# 05_BANK_5_6.net
KiCad netlist of a schematic drawn in Altium Designer
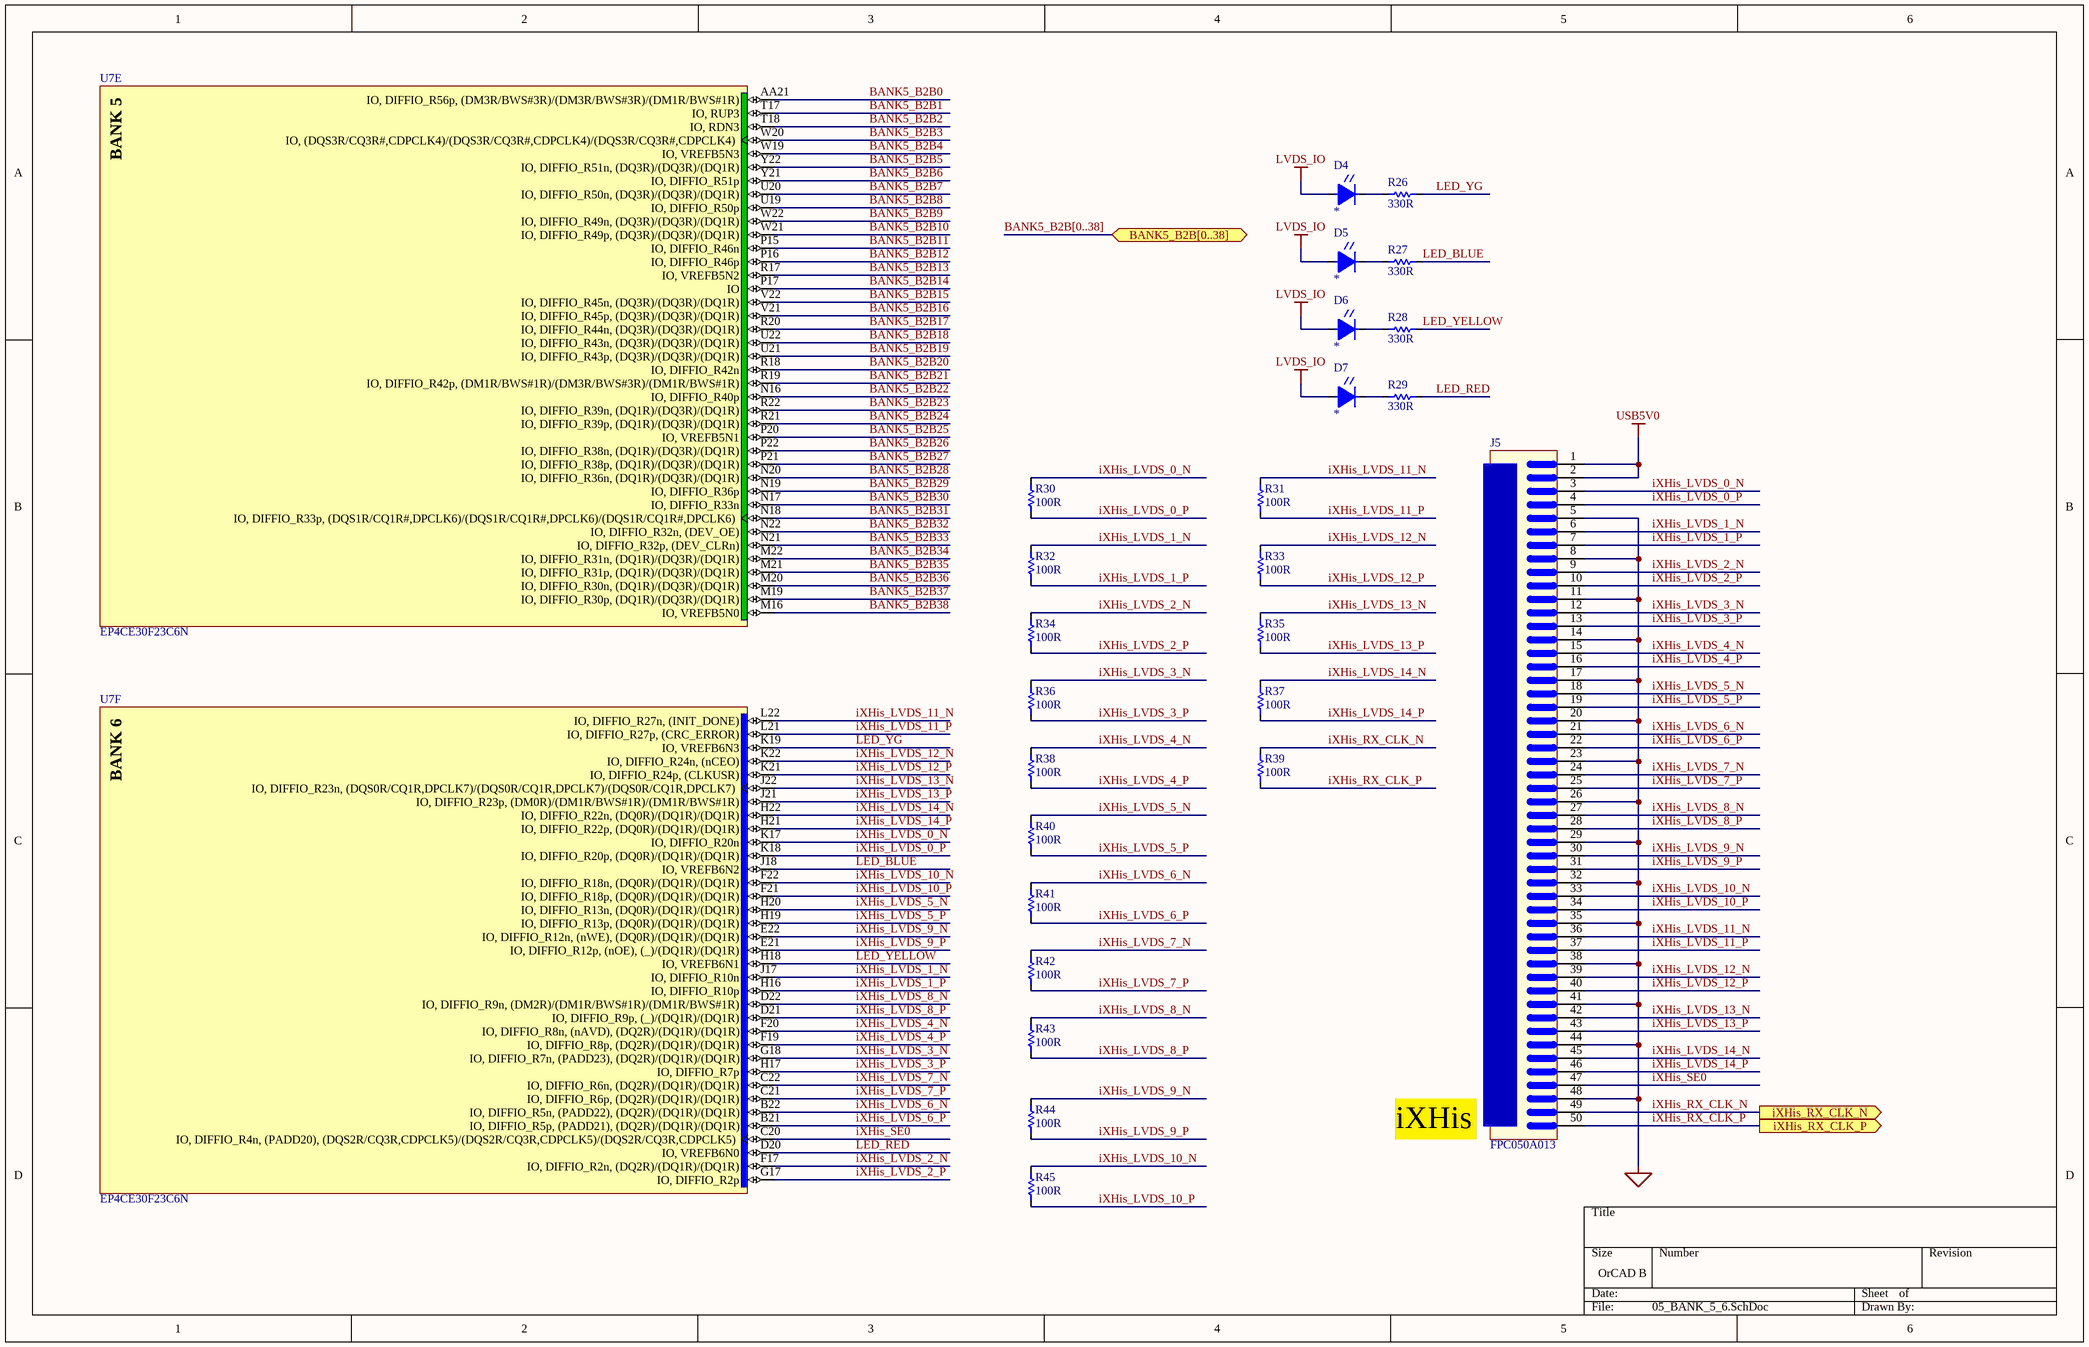
[diagram p0: 05_BANK_5_6.SchDoc]

(export (version "E")
  (design (tool "Eeschema 10.0.6"))
  (components
    (comp (ref "D4")
      (value "*")
      (footprint "LED0603")
      (description "LED,Yellow Green,2V,20mA,0603")
      (libsource (lib "AD15_schlib") (part "LED YellowGreen0603"))
    )
    (comp (ref "D5")
      (value "*")
      (footprint "LED0603")
      (description "LED,Blue,3.4V,20mA,0603")
      (libsource (lib "AD15_schlib") (part "LED Blue0603"))
    )
    (comp (ref "D6")
      (value "*")
      (footprint "LED0603")
      (description "LED,Yellow,2V,20mA,0603")
      (libsource (lib "AD15_schlib") (part "LED Yellow0603"))
    )
    (comp (ref "D7")
      (value "*")
      (footprint "LED0603")
      (description "LED,Super Red,2V,20mA,0603")
      (libsource (lib "AD15_schlib") (part "LED SuperRed0603"))
    )
    (comp (ref "J5")
      (value "FPC050A013")
      (footprint "FPC050A013")
      (description "FFC socket,50-Pin,Vertical,0.5mm Pitch,SMD")
      (libsource (lib "AD15_schlib") (part "FPC0.5mm_05"))
    )
    (comp (ref "R26")
      (value "330R")
      (footprint "R0402")
      (description "RES,330R,1%,1/16W,0402")
      (libsource (lib "R0402") (part "RES0111"))
    )
    (comp (ref "R27")
      (value "330R")
      (footprint "R0402")
      (description "RES,330R,1%,1/16W,0402")
      (libsource (lib "R0402") (part "RES0111"))
    )
    (comp (ref "R28")
      (value "330R")
      (footprint "R0402")
      (description "RES,330R,1%,1/16W,0402")
      (libsource (lib "R0402") (part "RES0111"))
    )
    (comp (ref "R29")
      (value "330R")
      (footprint "R0402")
      (description "RES,330R,1%,1/16W,0402")
      (libsource (lib "R0402") (part "RES0111"))
    )
    (comp (ref "R30")
      (value "100R")
      (footprint "R0402")
      (description "RES,100R,1%,1/16W,0402")
      (libsource (lib "R0402") (part "RES019"))
    )
    (comp (ref "R31")
      (value "100R")
      (footprint "R0402")
      (description "RES,100R,1%,1/16W,0402")
      (libsource (lib "R0402") (part "RES019"))
    )
    (comp (ref "R32")
      (value "100R")
      (footprint "R0402")
      (description "RES,100R,1%,1/16W,0402")
      (libsource (lib "R0402") (part "RES019"))
    )
    (comp (ref "R33")
      (value "100R")
      (footprint "R0402")
      (description "RES,100R,1%,1/16W,0402")
      (libsource (lib "R0402") (part "RES019"))
    )
    (comp (ref "R34")
      (value "100R")
      (footprint "R0402")
      (description "RES,100R,1%,1/16W,0402")
      (libsource (lib "R0402") (part "RES019"))
    )
    (comp (ref "R35")
      (value "100R")
      (footprint "R0402")
      (description "RES,100R,1%,1/16W,0402")
      (libsource (lib "R0402") (part "RES019"))
    )
    (comp (ref "R36")
      (value "100R")
      (footprint "R0402")
      (description "RES,100R,1%,1/16W,0402")
      (libsource (lib "R0402") (part "RES019"))
    )
    (comp (ref "R37")
      (value "100R")
      (footprint "R0402")
      (description "RES,100R,1%,1/16W,0402")
      (libsource (lib "R0402") (part "RES019"))
    )
    (comp (ref "R38")
      (value "100R")
      (footprint "R0402")
      (description "RES,100R,1%,1/16W,0402")
      (libsource (lib "R0402") (part "RES019"))
    )
    (comp (ref "R39")
      (value "100R")
      (footprint "R0402")
      (description "RES,100R,1%,1/16W,0402")
      (libsource (lib "R0402") (part "RES019"))
    )
    (comp (ref "R40")
      (value "100R")
      (footprint "R0402")
      (description "RES,100R,1%,1/16W,0402")
      (libsource (lib "R0402") (part "RES019"))
    )
    (comp (ref "R41")
      (value "100R")
      (footprint "R0402")
      (description "RES,100R,1%,1/16W,0402")
      (libsource (lib "R0402") (part "RES019"))
    )
    (comp (ref "R42")
      (value "100R")
      (footprint "R0402")
      (description "RES,100R,1%,1/16W,0402")
      (libsource (lib "R0402") (part "RES019"))
    )
    (comp (ref "R43")
      (value "100R")
      (footprint "R0402")
      (description "RES,100R,1%,1/16W,0402")
      (libsource (lib "R0402") (part "RES019"))
    )
    (comp (ref "R44")
      (value "100R")
      (footprint "R0402")
      (description "RES,100R,1%,1/16W,0402")
      (libsource (lib "R0402") (part "RES019"))
    )
    (comp (ref "R45")
      (value "100R")
      (footprint "R0402")
      (description "RES,100R,1%,1/16W,0402")
      (libsource (lib "R0402") (part "RES019"))
    )
    (comp (ref "U7")
      (value "EP4CE30F23C6N")
      (footprint "FBGA484_EP4CE30F23C6N")
      (description "IC,FPGA,28848 LEs,Speed-6,FBGA484")
      (libsource (lib "AD15_Altera_schlib") (part "EP4CE30F23C6N"))
    )
  )
  (nets
    (net (code "1") (name "/BANK5_B2B0") (class "Default")
      (node (ref "U7") (pin "AA21") (pinfunction "IO,_DIFFIO_R56p,_(DM3R/BWS#3R)/(DM3R/BWS#3R)/(DM1R/BWS#1R)_AA21") (pintype "bidirectional"))
    )
    (net (code "2") (name "/BANK5_B2B1") (class "Default")
      (node (ref "U7") (pin "T17") (pinfunction "IO,_RUP3_T17") (pintype "bidirectional"))
    )
    (net (code "3") (name "/BANK5_B2B2") (class "Default")
      (node (ref "U7") (pin "T18") (pinfunction "IO,_RDN3_T18") (pintype "bidirectional"))
    )
    (net (code "4") (name "/BANK5_B2B3") (class "Default")
      (node (ref "U7") (pin "W20") (pinfunction "IO,_(DQS3R/CQ3R#,CDPCLK4)/(DQS3R/CQ3R#,CDPCLK4)/(DQS3R/CQ3R#,CDPCLK4)_W20") (pintype "bidirectional"))
    )
    (net (code "5") (name "/BANK5_B2B4") (class "Default")
      (node (ref "U7") (pin "W19") (pinfunction "IO,_VREFB5N3_W19") (pintype "bidirectional"))
    )
    (net (code "6") (name "/BANK5_B2B5") (class "Default")
      (node (ref "U7") (pin "Y22") (pinfunction "IO,_DIFFIO_R51n,_(DQ3R)/(DQ3R)/(DQ1R)_Y22") (pintype "bidirectional"))
    )
    (net (code "7") (name "/BANK5_B2B6") (class "Default")
      (node (ref "U7") (pin "Y21") (pinfunction "IO,_DIFFIO_R51p_Y21") (pintype "bidirectional"))
    )
    (net (code "8") (name "/BANK5_B2B7") (class "Default")
      (node (ref "U7") (pin "U20") (pinfunction "IO,_DIFFIO_R50n,_(DQ3R)/(DQ3R)/(DQ1R)_U20") (pintype "bidirectional"))
    )
    (net (code "9") (name "/BANK5_B2B8") (class "Default")
      (node (ref "U7") (pin "U19") (pinfunction "IO,_DIFFIO_R50p_U19") (pintype "bidirectional"))
    )
    (net (code "10") (name "/BANK5_B2B9") (class "Default")
      (node (ref "U7") (pin "W22") (pinfunction "IO,_DIFFIO_R49n,_(DQ3R)/(DQ3R)/(DQ1R)_W22") (pintype "bidirectional"))
    )
    (net (code "11") (name "/BANK5_B2B10") (class "Default")
      (node (ref "U7") (pin "W21") (pinfunction "IO,_DIFFIO_R49p,_(DQ3R)/(DQ3R)/(DQ1R)_W21") (pintype "bidirectional"))
    )
    (net (code "12") (name "/BANK5_B2B11") (class "Default")
      (node (ref "U7") (pin "P15") (pinfunction "IO,_DIFFIO_R46n_P15") (pintype "bidirectional"))
    )
    (net (code "13") (name "/BANK5_B2B12") (class "Default")
      (node (ref "U7") (pin "P16") (pinfunction "IO,_DIFFIO_R46p_P16") (pintype "bidirectional"))
    )
    (net (code "14") (name "/BANK5_B2B13") (class "Default")
      (node (ref "U7") (pin "R17") (pinfunction "IO,_VREFB5N2_R17") (pintype "bidirectional"))
    )
    (net (code "15") (name "/BANK5_B2B14") (class "Default")
      (node (ref "U7") (pin "P17") (pinfunction "IO_P17") (pintype "bidirectional"))
    )
    (net (code "16") (name "/BANK5_B2B15") (class "Default")
      (node (ref "U7") (pin "V22") (pinfunction "IO,_DIFFIO_R45n,_(DQ3R)/(DQ3R)/(DQ1R)_V22") (pintype "bidirectional"))
    )
    (net (code "17") (name "/BANK5_B2B16") (class "Default")
      (node (ref "U7") (pin "V21") (pinfunction "IO,_DIFFIO_R45p,_(DQ3R)/(DQ3R)/(DQ1R)_V21") (pintype "bidirectional"))
    )
    (net (code "18") (name "/BANK5_B2B17") (class "Default")
      (node (ref "U7") (pin "R20") (pinfunction "IO,_DIFFIO_R44n,_(DQ3R)/(DQ3R)/(DQ1R)_R20") (pintype "bidirectional"))
    )
    (net (code "19") (name "/BANK5_B2B18") (class "Default")
      (node (ref "U7") (pin "U22") (pinfunction "IO,_DIFFIO_R43n,_(DQ3R)/(DQ3R)/(DQ1R)_U22") (pintype "bidirectional"))
    )
    (net (code "20") (name "/BANK5_B2B19") (class "Default")
      (node (ref "U7") (pin "U21") (pinfunction "IO,_DIFFIO_R43p,_(DQ3R)/(DQ3R)/(DQ1R)_U21") (pintype "bidirectional"))
    )
    (net (code "21") (name "/BANK5_B2B20") (class "Default")
      (node (ref "U7") (pin "R18") (pinfunction "IO,_DIFFIO_R42n_R18") (pintype "bidirectional"))
    )
    (net (code "22") (name "/BANK5_B2B21") (class "Default")
      (node (ref "U7") (pin "R19") (pinfunction "IO,_DIFFIO_R42p,_(DM1R/BWS#1R)/(DM3R/BWS#3R)/(DM1R/BWS#1R)_R19") (pintype "bidirectional"))
    )
    (net (code "23") (name "/BANK5_B2B22") (class "Default")
      (node (ref "U7") (pin "N16") (pinfunction "IO,_DIFFIO_R40p_N16") (pintype "bidirectional"))
    )
    (net (code "24") (name "/BANK5_B2B23") (class "Default")
      (node (ref "U7") (pin "R22") (pinfunction "IO,_DIFFIO_R39n,_(DQ1R)/(DQ3R)/(DQ1R)_R22") (pintype "bidirectional"))
    )
    (net (code "25") (name "/BANK5_B2B24") (class "Default")
      (node (ref "U7") (pin "R21") (pinfunction "IO,_DIFFIO_R39p,_(DQ1R)/(DQ3R)/(DQ1R)_R21") (pintype "bidirectional"))
    )
    (net (code "26") (name "/BANK5_B2B25") (class "Default")
      (node (ref "U7") (pin "P20") (pinfunction "IO,_VREFB5N1_P20") (pintype "bidirectional"))
    )
    (net (code "27") (name "/BANK5_B2B26") (class "Default")
      (node (ref "U7") (pin "P22") (pinfunction "IO,_DIFFIO_R38n,_(DQ1R)/(DQ3R)/(DQ1R)_P22") (pintype "bidirectional"))
    )
    (net (code "28") (name "/BANK5_B2B27") (class "Default")
      (node (ref "U7") (pin "P21") (pinfunction "IO,_DIFFIO_R38p,_(DQ1R)/(DQ3R)/(DQ1R)_P21") (pintype "bidirectional"))
    )
    (net (code "29") (name "/BANK5_B2B28") (class "Default")
      (node (ref "U7") (pin "N20") (pinfunction "IO,_DIFFIO_R36n,_(DQ1R)/(DQ3R)/(DQ1R)_N20") (pintype "bidirectional"))
    )
    (net (code "30") (name "/BANK5_B2B29") (class "Default")
      (node (ref "U7") (pin "N19") (pinfunction "IO,_DIFFIO_R36p_N19") (pintype "bidirectional"))
    )
    (net (code "31") (name "/BANK5_B2B30") (class "Default")
      (node (ref "U7") (pin "N17") (pinfunction "IO,_DIFFIO_R33n_N17") (pintype "bidirectional"))
    )
    (net (code "32") (name "/BANK5_B2B31") (class "Default")
      (node (ref "U7") (pin "N18") (pinfunction "IO,_DIFFIO_R33p,_(DQS1R/CQ1R#,DPCLK6)/(DQS1R/CQ1R#,DPCLK6)/(DQS1R/CQ1R#,DPCLK6)_N18") (pintype "bidirectional"))
    )
    (net (code "33") (name "/BANK5_B2B32") (class "Default")
      (node (ref "U7") (pin "N22") (pinfunction "IO,_DIFFIO_R32n,_(DEV_OE)_N22") (pintype "bidirectional"))
    )
    (net (code "34") (name "/BANK5_B2B33") (class "Default")
      (node (ref "U7") (pin "N21") (pinfunction "IO,_DIFFIO_R32p,_(DEV_CLRn)_N21") (pintype "bidirectional"))
    )
    (net (code "35") (name "/BANK5_B2B34") (class "Default")
      (node (ref "U7") (pin "M22") (pinfunction "IO,_DIFFIO_R31n,_(DQ1R)/(DQ3R)/(DQ1R)_M22") (pintype "bidirectional"))
    )
    (net (code "36") (name "/BANK5_B2B35") (class "Default")
      (node (ref "U7") (pin "M21") (pinfunction "IO,_DIFFIO_R31p,_(DQ1R)/(DQ3R)/(DQ1R)_M21") (pintype "bidirectional"))
    )
    (net (code "37") (name "/BANK5_B2B36") (class "Default")
      (node (ref "U7") (pin "M20") (pinfunction "IO,_DIFFIO_R30n,_(DQ1R)/(DQ3R)/(DQ1R)_M20") (pintype "bidirectional"))
    )
    (net (code "38") (name "/BANK5_B2B37") (class "Default")
      (node (ref "U7") (pin "M19") (pinfunction "IO,_DIFFIO_R30p,_(DQ1R)/(DQ3R)/(DQ1R)_M19") (pintype "bidirectional"))
    )
    (net (code "39") (name "/BANK5_B2B38") (class "Default")
      (node (ref "U7") (pin "M16") (pinfunction "IO,_VREFB5N0_M16") (pintype "bidirectional"))
    )
    (net (code "41") (name "/LED_BLUE") (class "Default")
      (node (ref "R27") (pin "2") (pinfunction "2_2") (pintype "passive"))
      (node (ref "U7") (pin "J18") (pinfunction "IO,_VREFB6N2_J18") (pintype "bidirectional"))
    )
    (net (code "42") (name "/LED_RED") (class "Default")
      (node (ref "R29") (pin "2") (pinfunction "2_2") (pintype "passive"))
      (node (ref "U7") (pin "D20") (pinfunction "IO,_VREFB6N0_D20") (pintype "bidirectional"))
    )
    (net (code "43") (name "/LED_YELLOW") (class "Default")
      (node (ref "R28") (pin "2") (pinfunction "2_2") (pintype "passive"))
      (node (ref "U7") (pin "H18") (pinfunction "IO,_VREFB6N1_H18") (pintype "bidirectional"))
    )
    (net (code "44") (name "/LED_YG") (class "Default")
      (node (ref "R26") (pin "2") (pinfunction "2_2") (pintype "passive"))
      (node (ref "U7") (pin "K19") (pinfunction "IO,_VREFB6N3_K19") (pintype "bidirectional"))
    )
    (net (code "45") (name "/iXHis_LVDS_0_N") (class "Default")
      (node (ref "J5") (pin "3") (pinfunction "2_3") (pintype "passive"))
      (node (ref "R30") (pin "2") (pinfunction "2_2") (pintype "passive"))
      (node (ref "U7") (pin "K17") (pinfunction "IO,_DIFFIO_R20n_K17") (pintype "bidirectional"))
    )
    (net (code "46") (name "/iXHis_LVDS_0_P") (class "Default")
      (node (ref "J5") (pin "4") (pinfunction "3_4") (pintype "passive"))
      (node (ref "R30") (pin "1") (pinfunction "0_1") (pintype "passive"))
      (node (ref "U7") (pin "K18") (pinfunction "IO,_DIFFIO_R20p,_(DQ0R)/(DQ1R)/(DQ1R)_K18") (pintype "bidirectional"))
    )
    (net (code "47") (name "/iXHis_LVDS_1_N") (class "Default")
      (node (ref "J5") (pin "6") (pinfunction "5_6") (pintype "passive"))
      (node (ref "R32") (pin "2") (pinfunction "2_2") (pintype "passive"))
      (node (ref "U7") (pin "J17") (pinfunction "IO,_DIFFIO_R10n_J17") (pintype "bidirectional"))
    )
    (net (code "48") (name "/iXHis_LVDS_1_P") (class "Default")
      (node (ref "J5") (pin "7") (pinfunction "6_7") (pintype "passive"))
      (node (ref "R32") (pin "1") (pinfunction "0_1") (pintype "passive"))
      (node (ref "U7") (pin "H16") (pinfunction "IO,_DIFFIO_R10p_H16") (pintype "bidirectional"))
    )
    (net (code "49") (name "/iXHis_LVDS_2_N") (class "Default")
      (node (ref "J5") (pin "9") (pinfunction "8_9") (pintype "passive"))
      (node (ref "R34") (pin "2") (pinfunction "2_2") (pintype "passive"))
      (node (ref "U7") (pin "F17") (pinfunction "IO,_DIFFIO_R2n,_(DQ2R)/(DQ1R)/(DQ1R)_F17") (pintype "bidirectional"))
    )
    (net (code "50") (name "/iXHis_LVDS_2_P") (class "Default")
      (node (ref "J5") (pin "10") (pinfunction "9_10") (pintype "passive"))
      (node (ref "R34") (pin "1") (pinfunction "0_1") (pintype "passive"))
      (node (ref "U7") (pin "G17") (pinfunction "IO,_DIFFIO_R2p_G17") (pintype "bidirectional"))
    )
    (net (code "51") (name "/iXHis_LVDS_3_N") (class "Default")
      (node (ref "J5") (pin "12") (pinfunction "12_12") (pintype "passive"))
      (node (ref "R36") (pin "2") (pinfunction "2_2") (pintype "passive"))
      (node (ref "U7") (pin "G18") (pinfunction "IO,_DIFFIO_R7n,_(PADD23),_(DQ2R)/(DQ1R)/(DQ1R)_G18") (pintype "bidirectional"))
    )
    (net (code "52") (name "/iXHis_LVDS_3_P") (class "Default")
      (node (ref "J5") (pin "13") (pinfunction "13_13") (pintype "passive"))
      (node (ref "R36") (pin "1") (pinfunction "0_1") (pintype "passive"))
      (node (ref "U7") (pin "H17") (pinfunction "IO,_DIFFIO_R7p_H17") (pintype "bidirectional"))
    )
    (net (code "53") (name "/iXHis_LVDS_4_N") (class "Default")
      (node (ref "J5") (pin "15") (pinfunction "15_15") (pintype "passive"))
      (node (ref "R38") (pin "2") (pinfunction "2_2") (pintype "passive"))
      (node (ref "U7") (pin "F20") (pinfunction "IO,_DIFFIO_R8n,_(nAVD),_(DQ2R)/(DQ1R)/(DQ1R)_F20") (pintype "bidirectional"))
    )
    (net (code "54") (name "/iXHis_LVDS_4_P") (class "Default")
      (node (ref "J5") (pin "16") (pinfunction "16_16") (pintype "passive"))
      (node (ref "R38") (pin "1") (pinfunction "0_1") (pintype "passive"))
      (node (ref "U7") (pin "F19") (pinfunction "IO,_DIFFIO_R8p,_(DQ2R)/(DQ1R)/(DQ1R)_F19") (pintype "bidirectional"))
    )
    (net (code "55") (name "/iXHis_LVDS_5_N") (class "Default")
      (node (ref "J5") (pin "18") (pinfunction "18_18") (pintype "passive"))
      (node (ref "R40") (pin "2") (pinfunction "2_2") (pintype "passive"))
      (node (ref "U7") (pin "H20") (pinfunction "IO,_DIFFIO_R13n,_(DQ0R)/(DQ1R)/(DQ1R)_H20") (pintype "bidirectional"))
    )
    (net (code "56") (name "/iXHis_LVDS_5_P") (class "Default")
      (node (ref "J5") (pin "19") (pinfunction "19_19") (pintype "passive"))
      (node (ref "R40") (pin "1") (pinfunction "0_1") (pintype "passive"))
      (node (ref "U7") (pin "H19") (pinfunction "IO,_DIFFIO_R13p,_(DQ0R)/(DQ1R)/(DQ1R)_H19") (pintype "bidirectional"))
    )
    (net (code "57") (name "/iXHis_LVDS_6_N") (class "Default")
      (node (ref "J5") (pin "21") (pinfunction "21_21") (pintype "passive"))
      (node (ref "R41") (pin "2") (pinfunction "2_2") (pintype "passive"))
      (node (ref "U7") (pin "B22") (pinfunction "IO,_DIFFIO_R5n,_(PADD22),_(DQ2R)/(DQ1R)/(DQ1R)_B22") (pintype "bidirectional"))
    )
    (net (code "58") (name "/iXHis_LVDS_6_P") (class "Default")
      (node (ref "J5") (pin "22") (pinfunction "22_22") (pintype "passive"))
      (node (ref "R41") (pin "1") (pinfunction "0_1") (pintype "passive"))
      (node (ref "U7") (pin "B21") (pinfunction "IO,_DIFFIO_R5p,_(PADD21),_(DQ2R)/(DQ1R)/(DQ1R)_B21") (pintype "bidirectional"))
    )
    (net (code "59") (name "/iXHis_LVDS_7_N") (class "Default")
      (node (ref "J5") (pin "24") (pinfunction "24_24") (pintype "passive"))
      (node (ref "R42") (pin "2") (pinfunction "2_2") (pintype "passive"))
      (node (ref "U7") (pin "C22") (pinfunction "IO,_DIFFIO_R6n,_(DQ2R)/(DQ1R)/(DQ1R)_C22") (pintype "bidirectional"))
    )
    (net (code "60") (name "/iXHis_LVDS_7_P") (class "Default")
      (node (ref "J5") (pin "25") (pinfunction "25_25") (pintype "passive"))
      (node (ref "R42") (pin "1") (pinfunction "0_1") (pintype "passive"))
      (node (ref "U7") (pin "C21") (pinfunction "IO,_DIFFIO_R6p,_(DQ2R)/(DQ1R)/(DQ1R)_C21") (pintype "bidirectional"))
    )
    (net (code "61") (name "/iXHis_LVDS_8_N") (class "Default")
      (node (ref "J5") (pin "27") (pinfunction "27_27") (pintype "passive"))
      (node (ref "R43") (pin "2") (pinfunction "2_2") (pintype "passive"))
      (node (ref "U7") (pin "D22") (pinfunction "IO,_DIFFIO_R9n,_(DM2R)/(DM1R/BWS#1R)/(DM1R/BWS#1R)_D22") (pintype "bidirectional"))
    )
    (net (code "62") (name "/iXHis_LVDS_8_P") (class "Default")
      (node (ref "J5") (pin "28") (pinfunction "28_28") (pintype "passive"))
      (node (ref "R43") (pin "1") (pinfunction "0_1") (pintype "passive"))
      (node (ref "U7") (pin "D21") (pinfunction "IO,_DIFFIO_R9p,_(_)/(DQ1R)/(DQ1R)_D21") (pintype "bidirectional"))
    )
    (net (code "63") (name "/iXHis_LVDS_9_N") (class "Default")
      (node (ref "J5") (pin "30") (pinfunction "30_30") (pintype "passive"))
      (node (ref "R44") (pin "2") (pinfunction "2_2") (pintype "passive"))
      (node (ref "U7") (pin "E22") (pinfunction "IO,_DIFFIO_R12n,_(nWE),_(DQ0R)/(DQ1R)/(DQ1R)_E22") (pintype "bidirectional"))
    )
    (net (code "64") (name "/iXHis_LVDS_9_P") (class "Default")
      (node (ref "J5") (pin "31") (pinfunction "31_31") (pintype "passive"))
      (node (ref "R44") (pin "1") (pinfunction "0_1") (pintype "passive"))
      (node (ref "U7") (pin "E21") (pinfunction "IO,_DIFFIO_R12p,_(nOE),_(_)/(DQ1R)/(DQ1R)_E21") (pintype "bidirectional"))
    )
    (net (code "65") (name "/iXHis_LVDS_10_N") (class "Default")
      (node (ref "J5") (pin "33") (pinfunction "33_33") (pintype "passive"))
      (node (ref "R45") (pin "2") (pinfunction "2_2") (pintype "passive"))
      (node (ref "U7") (pin "F22") (pinfunction "IO,_DIFFIO_R18n,_(DQ0R)/(DQ1R)/(DQ1R)_F22") (pintype "bidirectional"))
    )
    (net (code "66") (name "/iXHis_LVDS_10_P") (class "Default")
      (node (ref "J5") (pin "34") (pinfunction "34_34") (pintype "passive"))
      (node (ref "R45") (pin "1") (pinfunction "0_1") (pintype "passive"))
      (node (ref "U7") (pin "F21") (pinfunction "IO,_DIFFIO_R18p,_(DQ0R)/(DQ1R)/(DQ1R)_F21") (pintype "bidirectional"))
    )
    (net (code "67") (name "/iXHis_LVDS_11_N") (class "Default")
      (node (ref "J5") (pin "36") (pinfunction "36_36") (pintype "passive"))
      (node (ref "R31") (pin "2") (pinfunction "2_2") (pintype "passive"))
      (node (ref "U7") (pin "L22") (pinfunction "IO,_DIFFIO_R27n,_(INIT_DONE)_L22") (pintype "bidirectional"))
    )
    (net (code "68") (name "/iXHis_LVDS_11_P") (class "Default")
      (node (ref "J5") (pin "37") (pinfunction "37_37") (pintype "passive"))
      (node (ref "R31") (pin "1") (pinfunction "0_1") (pintype "passive"))
      (node (ref "U7") (pin "L21") (pinfunction "IO,_DIFFIO_R27p,_(CRC_ERROR)_L21") (pintype "bidirectional"))
    )
    (net (code "69") (name "/iXHis_LVDS_12_N") (class "Default")
      (node (ref "J5") (pin "39") (pinfunction "39_39") (pintype "passive"))
      (node (ref "R33") (pin "2") (pinfunction "2_2") (pintype "passive"))
      (node (ref "U7") (pin "K22") (pinfunction "IO,_DIFFIO_R24n,_(nCEO)_K22") (pintype "bidirectional"))
    )
    (net (code "70") (name "/iXHis_LVDS_12_P") (class "Default")
      (node (ref "J5") (pin "40") (pinfunction "40_40") (pintype "passive"))
      (node (ref "R33") (pin "1") (pinfunction "0_1") (pintype "passive"))
      (node (ref "U7") (pin "K21") (pinfunction "IO,_DIFFIO_R24p,_(CLKUSR)_K21") (pintype "bidirectional"))
    )
    (net (code "71") (name "/iXHis_LVDS_13_N") (class "Default")
      (node (ref "J5") (pin "42") (pinfunction "42_42") (pintype "passive"))
      (node (ref "R35") (pin "2") (pinfunction "2_2") (pintype "passive"))
      (node (ref "U7") (pin "J22") (pinfunction "IO,_DIFFIO_R23n,_(DQS0R/CQ1R,DPCLK7)/(DQS0R/CQ1R,DPCLK7)/(DQS0R/CQ1R,DPCLK7)_J22") (pintype "bidirectional"))
    )
    (net (code "72") (name "/iXHis_LVDS_13_P") (class "Default")
      (node (ref "J5") (pin "43") (pinfunction "43_43") (pintype "passive"))
      (node (ref "R35") (pin "1") (pinfunction "0_1") (pintype "passive"))
      (node (ref "U7") (pin "J21") (pinfunction "IO,_DIFFIO_R23p,_(DM0R)/(DM1R/BWS#1R)/(DM1R/BWS#1R)_J21") (pintype "bidirectional"))
    )
    (net (code "73") (name "/iXHis_LVDS_14_N") (class "Default")
      (node (ref "J5") (pin "45") (pinfunction "45_45") (pintype "passive"))
      (node (ref "R37") (pin "2") (pinfunction "2_2") (pintype "passive"))
      (node (ref "U7") (pin "H22") (pinfunction "IO,_DIFFIO_R22n,_(DQ0R)/(DQ1R)/(DQ1R)_H22") (pintype "bidirectional"))
    )
    (net (code "74") (name "/iXHis_LVDS_14_P") (class "Default")
      (node (ref "J5") (pin "46") (pinfunction "46_46") (pintype "passive"))
      (node (ref "R37") (pin "1") (pinfunction "0_1") (pintype "passive"))
      (node (ref "U7") (pin "H21") (pinfunction "IO,_DIFFIO_R22p,_(DQ0R)/(DQ1R)/(DQ1R)_H21") (pintype "bidirectional"))
    )
    (net (code "75") (name "/iXHis_RX_CLK_N") (class "Default")
      (node (ref "J5") (pin "49") (pinfunction "49_49") (pintype "passive"))
      (node (ref "R39") (pin "2") (pinfunction "2_2") (pintype "passive"))
    )
    (net (code "76") (name "/iXHis_RX_CLK_P") (class "Default")
      (node (ref "J5") (pin "50") (pinfunction "50_50") (pintype "passive"))
      (node (ref "R39") (pin "1") (pinfunction "0_1") (pintype "passive"))
    )
    (net (code "77") (name "/iXHis_SE0") (class "Default")
      (node (ref "J5") (pin "47") (pinfunction "47_47") (pintype "passive"))
      (node (ref "U7") (pin "C20") (pinfunction "IO,_DIFFIO_R4n,_(PADD20),_(DQS2R/CQ3R,CDPCLK5)/(DQS2R/CQ3R,CDPCLK5)/(DQS2R/CQ3R,CDPCLK5)_C20") (pintype "bidirectional"))
    )
    (net (code "78") (name "GND") (class "Default")
      (node (ref "J5") (pin "11") (pinfunction "11_11") (pintype "passive"))
      (node (ref "J5") (pin "14") (pinfunction "14_14") (pintype "passive"))
      (node (ref "J5") (pin "17") (pinfunction "17_17") (pintype "passive"))
      (node (ref "J5") (pin "20") (pinfunction "20_20") (pintype "passive"))
      (node (ref "J5") (pin "23") (pinfunction "23_23") (pintype "passive"))
      (node (ref "J5") (pin "26") (pinfunction "26_26") (pintype "passive"))
      (node (ref "J5") (pin "29") (pinfunction "29_29") (pintype "passive"))
      (node (ref "J5") (pin "32") (pinfunction "32_32") (pintype "passive"))
      (node (ref "J5") (pin "35") (pinfunction "35_35") (pintype "passive"))
      (node (ref "J5") (pin "38") (pinfunction "38_38") (pintype "passive"))
      (node (ref "J5") (pin "41") (pinfunction "41_41") (pintype "passive"))
      (node (ref "J5") (pin "44") (pinfunction "44_44") (pintype "passive"))
      (node (ref "J5") (pin "48") (pinfunction "48_48") (pintype "passive"))
      (node (ref "J5") (pin "5") (pinfunction "4_5") (pintype "passive"))
      (node (ref "J5") (pin "8") (pinfunction "7_8") (pintype "passive"))
    )
    (net (code "79") (name "LVDS_IO") (class "Default")
      (node (ref "D4") (pin "1") (pinfunction "L20_1") (pintype "passive"))
      (node (ref "D5") (pin "1") (pinfunction "L20_1") (pintype "passive"))
      (node (ref "D6") (pin "1") (pinfunction "L20_1") (pintype "passive"))
      (node (ref "D7") (pin "1") (pinfunction "L20_1") (pintype "passive"))
    )
    (net (code "80") (name "Net-(D4-L21)") (class "Default")
      (node (ref "D4") (pin "2") (pinfunction "L21_2") (pintype "passive"))
      (node (ref "R26") (pin "1") (pinfunction "0_1") (pintype "passive"))
    )
    (net (code "81") (name "Net-(D5-L21)") (class "Default")
      (node (ref "D5") (pin "2") (pinfunction "L21_2") (pintype "passive"))
      (node (ref "R27") (pin "1") (pinfunction "0_1") (pintype "passive"))
    )
    (net (code "82") (name "Net-(D6-L21)") (class "Default")
      (node (ref "D6") (pin "2") (pinfunction "L21_2") (pintype "passive"))
      (node (ref "R28") (pin "1") (pinfunction "0_1") (pintype "passive"))
    )
    (net (code "83") (name "Net-(D7-L21)") (class "Default")
      (node (ref "D7") (pin "2") (pinfunction "L21_2") (pintype "passive"))
      (node (ref "R29") (pin "1") (pinfunction "0_1") (pintype "passive"))
    )
    (net (code "84") (name "USB5V0") (class "Default")
      (node (ref "J5") (pin "1") (pinfunction "0_1") (pintype "passive"))
      (node (ref "J5") (pin "2") (pinfunction "1_2") (pintype "passive"))
    )
  )
)
